# BIT_6.net
KiCad netlist of a schematic drawn in EasyEDA
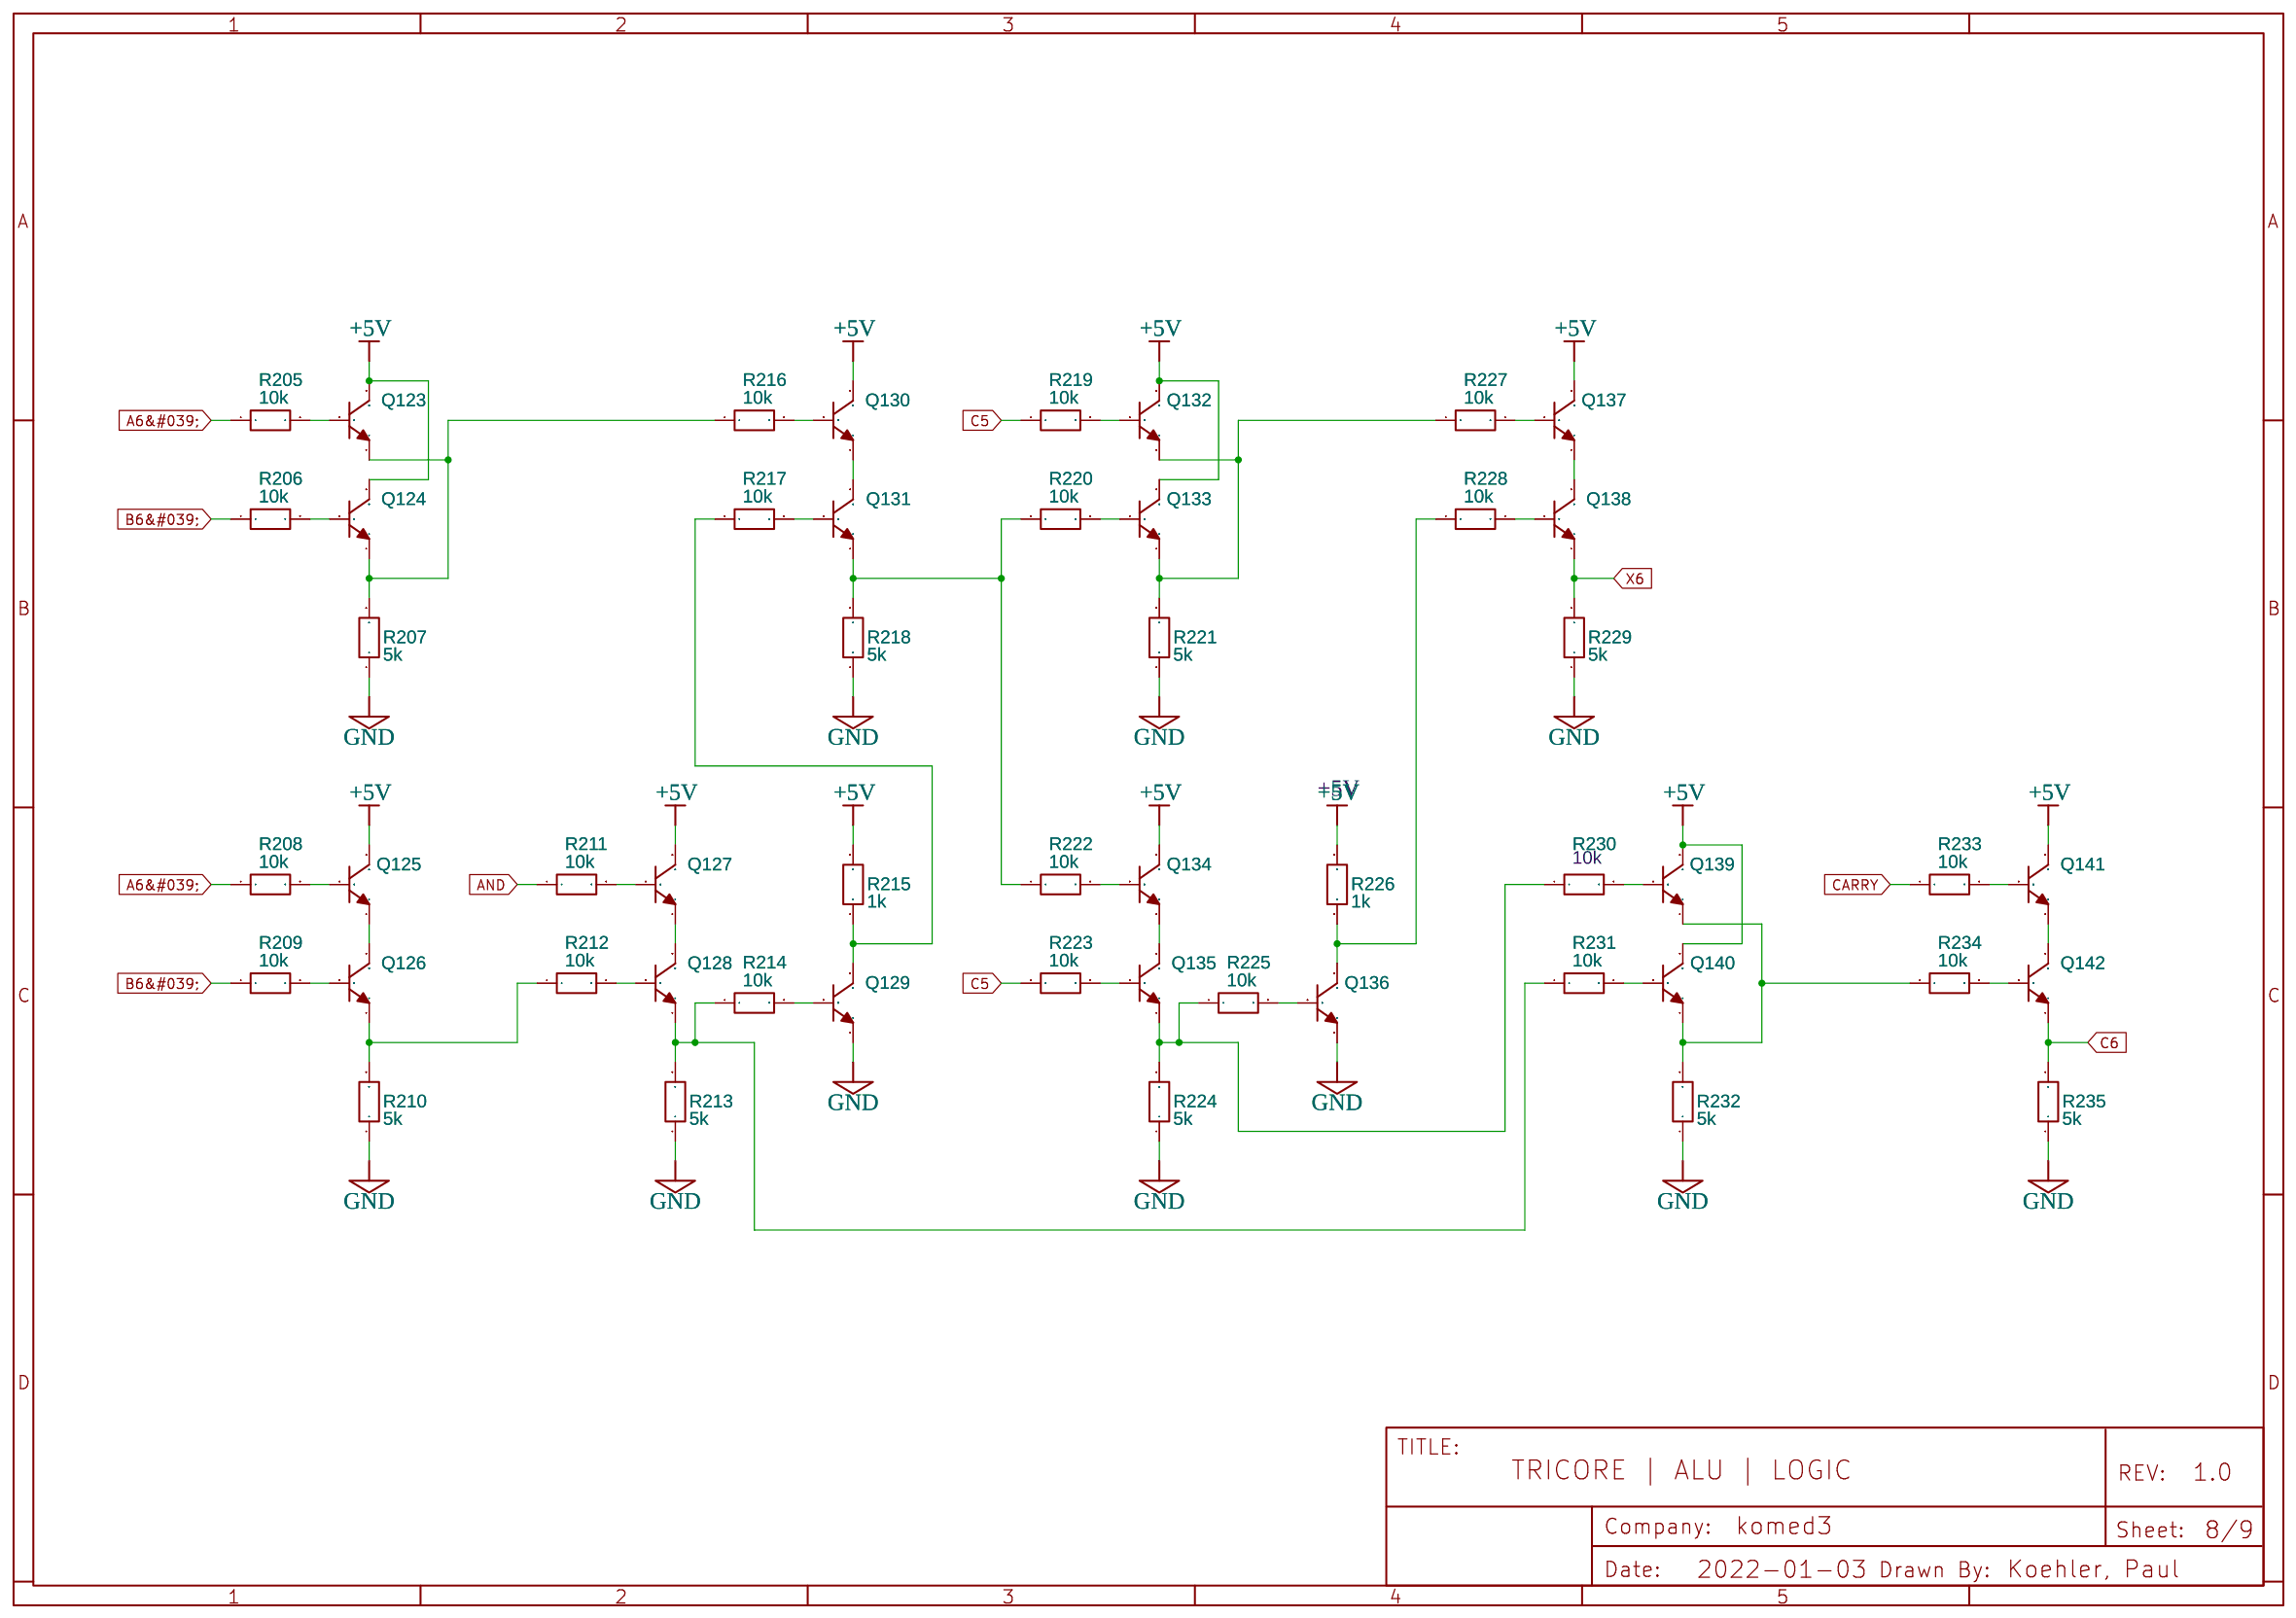
[diagram p0: schematic sheet]

(export (version "E")
  (design (tool "Eeschema 10.0.6"))
  (components
    (comp (ref "Q123")
      (value "2N3904(TO-92)")
      (fields (field (name "BOM_Manufacturer Part") "2N3904") (field (name "BOM_Supplier Part") "C118538"))
      (libsource (lib "") (part "2N3904(TO-92)"))
    )
    (comp (ref "Q124")
      (value "2N3904(TO-92)")
      (fields (field (name "BOM_Manufacturer Part") "2N3904") (field (name "BOM_Supplier Part") "C118538"))
      (libsource (lib "") (part "2N3904(TO-92)"))
    )
    (comp (ref "Q125")
      (value "2N3904(TO-92)")
      (fields (field (name "BOM_Manufacturer Part") "2N3904") (field (name "BOM_Supplier Part") "C118538"))
      (libsource (lib "") (part "2N3904(TO-92)"))
    )
    (comp (ref "Q126")
      (value "2N3904(TO-92)")
      (fields (field (name "BOM_Manufacturer Part") "2N3904") (field (name "BOM_Supplier Part") "C118538"))
      (libsource (lib "") (part "2N3904(TO-92)"))
    )
    (comp (ref "Q127")
      (value "2N3904(TO-92)")
      (fields (field (name "BOM_Manufacturer Part") "2N3904") (field (name "BOM_Supplier Part") "C118538"))
      (libsource (lib "") (part "2N3904(TO-92)"))
    )
    (comp (ref "Q128")
      (value "2N3904(TO-92)")
      (fields (field (name "BOM_Manufacturer Part") "2N3904") (field (name "BOM_Supplier Part") "C118538"))
      (libsource (lib "") (part "2N3904(TO-92)"))
    )
    (comp (ref "Q129")
      (value "2N3904(TO-92)")
      (fields (field (name "BOM_Manufacturer Part") "2N3904") (field (name "BOM_Supplier Part") "C118538"))
      (libsource (lib "") (part "2N3904(TO-92)"))
    )
    (comp (ref "Q130")
      (value "2N3904(TO-92)")
      (fields (field (name "BOM_Manufacturer Part") "2N3904") (field (name "BOM_Supplier Part") "C118538"))
      (libsource (lib "") (part "2N3904(TO-92)"))
    )
    (comp (ref "Q131")
      (value "2N3904(TO-92)")
      (fields (field (name "BOM_Manufacturer Part") "2N3904") (field (name "BOM_Supplier Part") "C118538"))
      (libsource (lib "") (part "2N3904(TO-92)"))
    )
    (comp (ref "Q132")
      (value "2N3904(TO-92)")
      (fields (field (name "BOM_Manufacturer Part") "2N3904") (field (name "BOM_Supplier Part") "C118538"))
      (libsource (lib "") (part "2N3904(TO-92)"))
    )
    (comp (ref "Q133")
      (value "2N3904(TO-92)")
      (fields (field (name "BOM_Manufacturer Part") "2N3904") (field (name "BOM_Supplier Part") "C118538"))
      (libsource (lib "") (part "2N3904(TO-92)"))
    )
    (comp (ref "Q134")
      (value "2N3904(TO-92)")
      (fields (field (name "BOM_Manufacturer Part") "2N3904") (field (name "BOM_Supplier Part") "C118538"))
      (libsource (lib "") (part "2N3904(TO-92)"))
    )
    (comp (ref "Q135")
      (value "2N3904(TO-92)")
      (fields (field (name "BOM_Manufacturer Part") "2N3904") (field (name "BOM_Supplier Part") "C118538"))
      (libsource (lib "") (part "2N3904(TO-92)"))
    )
    (comp (ref "Q136")
      (value "2N3904(TO-92)")
      (fields (field (name "BOM_Manufacturer Part") "2N3904") (field (name "BOM_Supplier Part") "C118538"))
      (libsource (lib "") (part "2N3904(TO-92)"))
    )
    (comp (ref "Q137")
      (value "2N3904(TO-92)")
      (fields (field (name "BOM_Manufacturer Part") "2N3904") (field (name "BOM_Supplier Part") "C118538"))
      (libsource (lib "") (part "2N3904(TO-92)"))
    )
    (comp (ref "Q138")
      (value "2N3904(TO-92)")
      (fields (field (name "BOM_Manufacturer Part") "2N3904") (field (name "BOM_Supplier Part") "C118538"))
      (libsource (lib "") (part "2N3904(TO-92)"))
    )
    (comp (ref "Q139")
      (value "2N3904(TO-92)")
      (fields (field (name "BOM_Manufacturer Part") "2N3904") (field (name "BOM_Supplier Part") "C118538"))
      (libsource (lib "") (part "2N3904(TO-92)"))
    )
    (comp (ref "Q140")
      (value "2N3904(TO-92)")
      (fields (field (name "BOM_Manufacturer Part") "2N3904") (field (name "BOM_Supplier Part") "C118538"))
      (libsource (lib "") (part "2N3904(TO-92)"))
    )
    (comp (ref "Q141")
      (value "2N3904(TO-92)")
      (fields (field (name "BOM_Manufacturer Part") "2N3904") (field (name "BOM_Supplier Part") "C118538"))
      (libsource (lib "") (part "2N3904(TO-92)"))
    )
    (comp (ref "Q142")
      (value "2N3904(TO-92)")
      (fields (field (name "BOM_Manufacturer Part") "2N3904") (field (name "BOM_Supplier Part") "C118538"))
      (libsource (lib "") (part "2N3904(TO-92)"))
    )
    (comp (ref "R205") (value "10k") (libsource (lib "") (part "R_AXIAL-0.3_EU")))
    (comp (ref "R206") (value "10k") (libsource (lib "") (part "R_AXIAL-0.3_EU")))
    (comp (ref "R207") (value "5k") (libsource (lib "") (part "R_AXIAL-0.3_EU_1")))
    (comp (ref "R208") (value "10k") (libsource (lib "") (part "R_AXIAL-0.3_EU")))
    (comp (ref "R209") (value "10k") (libsource (lib "") (part "R_AXIAL-0.3_EU")))
    (comp (ref "R210") (value "5k") (libsource (lib "") (part "R_AXIAL-0.3_EU_1")))
    (comp (ref "R211") (value "10k") (libsource (lib "") (part "R_AXIAL-0.3_EU")))
    (comp (ref "R212") (value "10k") (libsource (lib "") (part "R_AXIAL-0.3_EU")))
    (comp (ref "R213") (value "5k") (libsource (lib "") (part "R_AXIAL-0.3_EU_1")))
    (comp (ref "R214") (value "10k") (libsource (lib "") (part "R_AXIAL-0.3_EU")))
    (comp (ref "R215") (value "1k") (libsource (lib "") (part "R_AXIAL-0.3_EU_1")))
    (comp (ref "R216") (value "10k") (libsource (lib "") (part "R_AXIAL-0.3_EU")))
    (comp (ref "R217") (value "10k") (libsource (lib "") (part "R_AXIAL-0.3_EU")))
    (comp (ref "R218") (value "5k") (libsource (lib "") (part "R_AXIAL-0.3_EU_1")))
    (comp (ref "R219") (value "10k") (libsource (lib "") (part "R_AXIAL-0.3_EU")))
    (comp (ref "R220") (value "10k") (libsource (lib "") (part "R_AXIAL-0.3_EU")))
    (comp (ref "R221") (value "5k") (libsource (lib "") (part "R_AXIAL-0.3_EU_1")))
    (comp (ref "R222") (value "10k") (libsource (lib "") (part "R_AXIAL-0.3_EU")))
    (comp (ref "R223") (value "10k") (libsource (lib "") (part "R_AXIAL-0.3_EU")))
    (comp (ref "R224") (value "5k") (libsource (lib "") (part "R_AXIAL-0.3_EU_1")))
    (comp (ref "R225") (value "10k") (libsource (lib "") (part "R_AXIAL-0.3_EU")))
    (comp (ref "R226") (value "1k") (libsource (lib "") (part "R_AXIAL-0.3_EU_1")))
    (comp (ref "R227") (value "10k") (libsource (lib "") (part "R_AXIAL-0.3_EU")))
    (comp (ref "R228") (value "10k") (libsource (lib "") (part "R_AXIAL-0.3_EU")))
    (comp (ref "R229") (value "5k") (libsource (lib "") (part "R_AXIAL-0.3_EU_1")))
    (comp (ref "R230") (value "R224W") (libsource (lib "") (part "R_AXIAL-0.3_EU")))
    (comp (ref "R231") (value "10k") (libsource (lib "") (part "R_AXIAL-0.3_EU")))
    (comp (ref "R232") (value "5k") (libsource (lib "") (part "R_AXIAL-0.3_EU_1")))
    (comp (ref "R233") (value "10k") (libsource (lib "") (part "R_AXIAL-0.3_EU")))
    (comp (ref "R234") (value "10k") (libsource (lib "") (part "R_AXIAL-0.3_EU")))
    (comp (ref "R235") (value "5k") (libsource (lib "") (part "R_AXIAL-0.3_EU_1")))
  )
  (nets
    (net (code "1") (name "+5V") (class "Default")
      (node (ref "Q123") (pin "3") (pinfunction "C_3") (pintype "unspecified"))
      (node (ref "Q124") (pin "3") (pinfunction "C_3") (pintype "unspecified"))
      (node (ref "Q125") (pin "3") (pinfunction "C_3") (pintype "unspecified"))
      (node (ref "Q127") (pin "3") (pinfunction "C_3") (pintype "unspecified"))
      (node (ref "Q130") (pin "3") (pinfunction "C_3") (pintype "unspecified"))
      (node (ref "Q132") (pin "3") (pinfunction "C_3") (pintype "unspecified"))
      (node (ref "Q133") (pin "3") (pinfunction "C_3") (pintype "unspecified"))
      (node (ref "Q134") (pin "3") (pinfunction "C_3") (pintype "unspecified"))
      (node (ref "Q137") (pin "3") (pinfunction "C_3") (pintype "unspecified"))
      (node (ref "Q139") (pin "3") (pinfunction "C_3") (pintype "unspecified"))
      (node (ref "Q140") (pin "3") (pinfunction "C_3") (pintype "unspecified"))
      (node (ref "Q141") (pin "3") (pinfunction "C_3") (pintype "unspecified"))
      (node (ref "R215") (pin "2") (pinfunction "2_2") (pintype "unspecified"))
      (node (ref "R226") (pin "2") (pinfunction "2_2") (pintype "unspecified"))
    )
    (net (code "2") (name "A6&#039;") (class "Default")
      (node (ref "R205") (pin "1") (pinfunction "1_1") (pintype "unspecified"))
      (node (ref "R208") (pin "1") (pinfunction "1_1") (pintype "unspecified"))
    )
    (net (code "3") (name "AND") (class "Default")
      (node (ref "R211") (pin "1") (pinfunction "1_1") (pintype "unspecified"))
    )
    (net (code "4") (name "B6&#039;") (class "Default")
      (node (ref "R206") (pin "1") (pinfunction "1_1") (pintype "unspecified"))
      (node (ref "R209") (pin "1") (pinfunction "1_1") (pintype "unspecified"))
    )
    (net (code "5") (name "C5") (class "Default")
      (node (ref "R219") (pin "1") (pinfunction "1_1") (pintype "unspecified"))
      (node (ref "R223") (pin "1") (pinfunction "1_1") (pintype "unspecified"))
    )
    (net (code "6") (name "C6") (class "Default")
      (node (ref "Q142") (pin "1") (pinfunction "E_1") (pintype "unspecified"))
      (node (ref "R235") (pin "2") (pinfunction "2_2") (pintype "unspecified"))
    )
    (net (code "7") (name "CARRY") (class "Default")
      (node (ref "R233") (pin "1") (pinfunction "1_1") (pintype "unspecified"))
    )
    (net (code "8") (name "GND") (class "Default")
      (node (ref "Q129") (pin "1") (pinfunction "E_1") (pintype "unspecified"))
      (node (ref "Q136") (pin "1") (pinfunction "E_1") (pintype "unspecified"))
      (node (ref "R207") (pin "1") (pinfunction "1_1") (pintype "unspecified"))
      (node (ref "R210") (pin "1") (pinfunction "1_1") (pintype "unspecified"))
      (node (ref "R213") (pin "1") (pinfunction "1_1") (pintype "unspecified"))
      (node (ref "R218") (pin "1") (pinfunction "1_1") (pintype "unspecified"))
      (node (ref "R221") (pin "1") (pinfunction "1_1") (pintype "unspecified"))
      (node (ref "R224") (pin "1") (pinfunction "1_1") (pintype "unspecified"))
      (node (ref "R229") (pin "1") (pinfunction "1_1") (pintype "unspecified"))
      (node (ref "R232") (pin "1") (pinfunction "1_1") (pintype "unspecified"))
      (node (ref "R235") (pin "1") (pinfunction "1_1") (pintype "unspecified"))
    )
    (net (code "9") (name "Net-(Q123-B)") (class "Default")
      (node (ref "Q123") (pin "2") (pinfunction "B_2") (pintype "unspecified"))
      (node (ref "R205") (pin "2") (pinfunction "2_2") (pintype "unspecified"))
    )
    (net (code "10") (name "Net-(Q123-E)") (class "Default")
      (node (ref "Q123") (pin "1") (pinfunction "E_1") (pintype "unspecified"))
      (node (ref "Q124") (pin "1") (pinfunction "E_1") (pintype "unspecified"))
      (node (ref "R207") (pin "2") (pinfunction "2_2") (pintype "unspecified"))
      (node (ref "R216") (pin "1") (pinfunction "1_1") (pintype "unspecified"))
    )
    (net (code "11") (name "Net-(Q124-B)") (class "Default")
      (node (ref "Q124") (pin "2") (pinfunction "B_2") (pintype "unspecified"))
      (node (ref "R206") (pin "2") (pinfunction "2_2") (pintype "unspecified"))
    )
    (net (code "12") (name "Net-(Q125-B)") (class "Default")
      (node (ref "Q125") (pin "2") (pinfunction "B_2") (pintype "unspecified"))
      (node (ref "R208") (pin "2") (pinfunction "2_2") (pintype "unspecified"))
    )
    (net (code "13") (name "Net-(Q125-E)") (class "Default")
      (node (ref "Q125") (pin "1") (pinfunction "E_1") (pintype "unspecified"))
      (node (ref "Q126") (pin "3") (pinfunction "C_3") (pintype "unspecified"))
    )
    (net (code "14") (name "Net-(Q126-B)") (class "Default")
      (node (ref "Q126") (pin "2") (pinfunction "B_2") (pintype "unspecified"))
      (node (ref "R209") (pin "2") (pinfunction "2_2") (pintype "unspecified"))
    )
    (net (code "15") (name "Net-(Q126-E)") (class "Default")
      (node (ref "Q126") (pin "1") (pinfunction "E_1") (pintype "unspecified"))
      (node (ref "R210") (pin "2") (pinfunction "2_2") (pintype "unspecified"))
      (node (ref "R212") (pin "1") (pinfunction "1_1") (pintype "unspecified"))
    )
    (net (code "16") (name "Net-(Q127-B)") (class "Default")
      (node (ref "Q127") (pin "2") (pinfunction "B_2") (pintype "unspecified"))
      (node (ref "R211") (pin "2") (pinfunction "2_2") (pintype "unspecified"))
    )
    (net (code "17") (name "Net-(Q127-E)") (class "Default")
      (node (ref "Q127") (pin "1") (pinfunction "E_1") (pintype "unspecified"))
      (node (ref "Q128") (pin "3") (pinfunction "C_3") (pintype "unspecified"))
    )
    (net (code "18") (name "Net-(Q128-B)") (class "Default")
      (node (ref "Q128") (pin "2") (pinfunction "B_2") (pintype "unspecified"))
      (node (ref "R212") (pin "2") (pinfunction "2_2") (pintype "unspecified"))
    )
    (net (code "19") (name "Net-(Q128-E)") (class "Default")
      (node (ref "Q128") (pin "1") (pinfunction "E_1") (pintype "unspecified"))
      (node (ref "R213") (pin "2") (pinfunction "2_2") (pintype "unspecified"))
      (node (ref "R214") (pin "1") (pinfunction "1_1") (pintype "unspecified"))
      (node (ref "R231") (pin "1") (pinfunction "1_1") (pintype "unspecified"))
    )
    (net (code "20") (name "Net-(Q129-B)") (class "Default")
      (node (ref "Q129") (pin "2") (pinfunction "B_2") (pintype "unspecified"))
      (node (ref "R214") (pin "2") (pinfunction "2_2") (pintype "unspecified"))
    )
    (net (code "21") (name "Net-(Q129-C)") (class "Default")
      (node (ref "Q129") (pin "3") (pinfunction "C_3") (pintype "unspecified"))
      (node (ref "R215") (pin "1") (pinfunction "1_1") (pintype "unspecified"))
      (node (ref "R217") (pin "1") (pinfunction "1_1") (pintype "unspecified"))
    )
    (net (code "22") (name "Net-(Q130-B)") (class "Default")
      (node (ref "Q130") (pin "2") (pinfunction "B_2") (pintype "unspecified"))
      (node (ref "R216") (pin "2") (pinfunction "2_2") (pintype "unspecified"))
    )
    (net (code "23") (name "Net-(Q130-E)") (class "Default")
      (node (ref "Q130") (pin "1") (pinfunction "E_1") (pintype "unspecified"))
      (node (ref "Q131") (pin "3") (pinfunction "C_3") (pintype "unspecified"))
    )
    (net (code "24") (name "Net-(Q131-B)") (class "Default")
      (node (ref "Q131") (pin "2") (pinfunction "B_2") (pintype "unspecified"))
      (node (ref "R217") (pin "2") (pinfunction "2_2") (pintype "unspecified"))
    )
    (net (code "25") (name "Net-(Q131-E)") (class "Default")
      (node (ref "Q131") (pin "1") (pinfunction "E_1") (pintype "unspecified"))
      (node (ref "R218") (pin "2") (pinfunction "2_2") (pintype "unspecified"))
      (node (ref "R220") (pin "1") (pinfunction "1_1") (pintype "unspecified"))
      (node (ref "R222") (pin "1") (pinfunction "1_1") (pintype "unspecified"))
    )
    (net (code "26") (name "Net-(Q132-B)") (class "Default")
      (node (ref "Q132") (pin "2") (pinfunction "B_2") (pintype "unspecified"))
      (node (ref "R219") (pin "2") (pinfunction "2_2") (pintype "unspecified"))
    )
    (net (code "27") (name "Net-(Q132-E)") (class "Default")
      (node (ref "Q132") (pin "1") (pinfunction "E_1") (pintype "unspecified"))
      (node (ref "Q133") (pin "1") (pinfunction "E_1") (pintype "unspecified"))
      (node (ref "R221") (pin "2") (pinfunction "2_2") (pintype "unspecified"))
      (node (ref "R227") (pin "1") (pinfunction "1_1") (pintype "unspecified"))
    )
    (net (code "28") (name "Net-(Q133-B)") (class "Default")
      (node (ref "Q133") (pin "2") (pinfunction "B_2") (pintype "unspecified"))
      (node (ref "R220") (pin "2") (pinfunction "2_2") (pintype "unspecified"))
    )
    (net (code "29") (name "Net-(Q134-B)") (class "Default")
      (node (ref "Q134") (pin "2") (pinfunction "B_2") (pintype "unspecified"))
      (node (ref "R222") (pin "2") (pinfunction "2_2") (pintype "unspecified"))
    )
    (net (code "30") (name "Net-(Q134-E)") (class "Default")
      (node (ref "Q134") (pin "1") (pinfunction "E_1") (pintype "unspecified"))
      (node (ref "Q135") (pin "3") (pinfunction "C_3") (pintype "unspecified"))
    )
    (net (code "31") (name "Net-(Q135-B)") (class "Default")
      (node (ref "Q135") (pin "2") (pinfunction "B_2") (pintype "unspecified"))
      (node (ref "R223") (pin "2") (pinfunction "2_2") (pintype "unspecified"))
    )
    (net (code "32") (name "Net-(Q135-E)") (class "Default")
      (node (ref "Q135") (pin "1") (pinfunction "E_1") (pintype "unspecified"))
      (node (ref "R224") (pin "2") (pinfunction "2_2") (pintype "unspecified"))
      (node (ref "R225") (pin "1") (pinfunction "1_1") (pintype "unspecified"))
      (node (ref "R230") (pin "1") (pinfunction "1_1") (pintype "unspecified"))
    )
    (net (code "33") (name "Net-(Q136-B)") (class "Default")
      (node (ref "Q136") (pin "2") (pinfunction "B_2") (pintype "unspecified"))
      (node (ref "R225") (pin "2") (pinfunction "2_2") (pintype "unspecified"))
    )
    (net (code "34") (name "Net-(Q136-C)") (class "Default")
      (node (ref "Q136") (pin "3") (pinfunction "C_3") (pintype "unspecified"))
      (node (ref "R226") (pin "1") (pinfunction "1_1") (pintype "unspecified"))
      (node (ref "R228") (pin "1") (pinfunction "1_1") (pintype "unspecified"))
    )
    (net (code "35") (name "Net-(Q137-B)") (class "Default")
      (node (ref "Q137") (pin "2") (pinfunction "B_2") (pintype "unspecified"))
      (node (ref "R227") (pin "2") (pinfunction "2_2") (pintype "unspecified"))
    )
    (net (code "36") (name "Net-(Q137-E)") (class "Default")
      (node (ref "Q137") (pin "1") (pinfunction "E_1") (pintype "unspecified"))
      (node (ref "Q138") (pin "3") (pinfunction "C_3") (pintype "unspecified"))
    )
    (net (code "37") (name "Net-(Q138-B)") (class "Default")
      (node (ref "Q138") (pin "2") (pinfunction "B_2") (pintype "unspecified"))
      (node (ref "R228") (pin "2") (pinfunction "2_2") (pintype "unspecified"))
    )
    (net (code "38") (name "Net-(Q139-B)") (class "Default")
      (node (ref "Q139") (pin "2") (pinfunction "B_2") (pintype "unspecified"))
      (node (ref "R230") (pin "2") (pinfunction "2_2") (pintype "unspecified"))
    )
    (net (code "39") (name "Net-(Q139-E)") (class "Default")
      (node (ref "Q139") (pin "1") (pinfunction "E_1") (pintype "unspecified"))
      (node (ref "Q140") (pin "1") (pinfunction "E_1") (pintype "unspecified"))
      (node (ref "R232") (pin "2") (pinfunction "2_2") (pintype "unspecified"))
      (node (ref "R234") (pin "1") (pinfunction "1_1") (pintype "unspecified"))
    )
    (net (code "40") (name "Net-(Q140-B)") (class "Default")
      (node (ref "Q140") (pin "2") (pinfunction "B_2") (pintype "unspecified"))
      (node (ref "R231") (pin "2") (pinfunction "2_2") (pintype "unspecified"))
    )
    (net (code "41") (name "Net-(Q141-B)") (class "Default")
      (node (ref "Q141") (pin "2") (pinfunction "B_2") (pintype "unspecified"))
      (node (ref "R233") (pin "2") (pinfunction "2_2") (pintype "unspecified"))
    )
    (net (code "42") (name "Net-(Q141-E)") (class "Default")
      (node (ref "Q141") (pin "1") (pinfunction "E_1") (pintype "unspecified"))
      (node (ref "Q142") (pin "3") (pinfunction "C_3") (pintype "unspecified"))
    )
    (net (code "43") (name "Net-(Q142-B)") (class "Default")
      (node (ref "Q142") (pin "2") (pinfunction "B_2") (pintype "unspecified"))
      (node (ref "R234") (pin "2") (pinfunction "2_2") (pintype "unspecified"))
    )
    (net (code "44") (name "X6") (class "Default")
      (node (ref "Q138") (pin "1") (pinfunction "E_1") (pintype "unspecified"))
      (node (ref "R229") (pin "2") (pinfunction "2_2") (pintype "unspecified"))
    )
  )
)
